# led_driver_iw339_v1.net
KiCad netlist of a schematic drawn in EAGLE
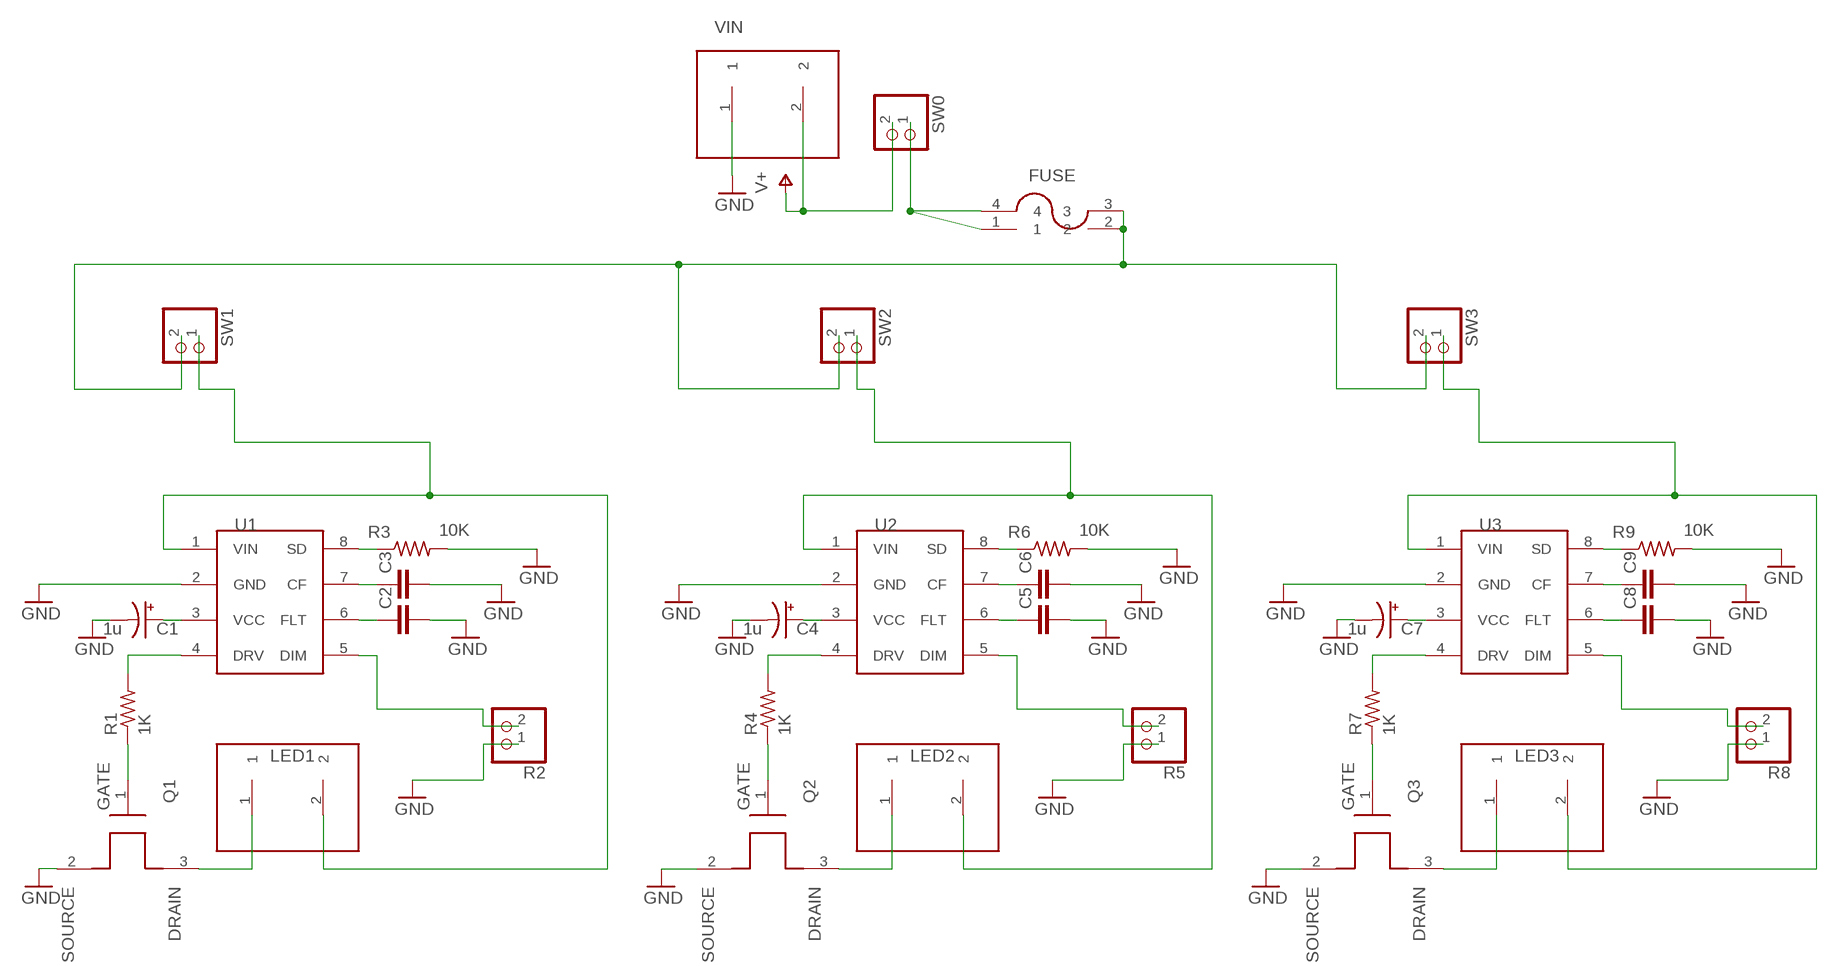
[diagram p0: schematic, sheet 1]

(export (version "E")
  (design (tool "Eeschema 10.0.6"))
  (components
    (comp (ref "C1")
      (value "1u")
      (footprint "eagle-import:E2-5")
      (libsource (lib "eagle-import") (part "CPOL-USE2-5"))
    )
    (comp (ref "C2")
      (value "0.1u")
      (footprint "eagle-import:C050-025X075")
      (libsource (lib "eagle-import") (part "THD_CAP"))
    )
    (comp (ref "C3")
      (value "1n")
      (footprint "eagle-import:C050-025X075")
      (libsource (lib "eagle-import") (part "THD_CAP"))
    )
    (comp (ref "C4")
      (value "1u")
      (footprint "eagle-import:E2-5")
      (libsource (lib "eagle-import") (part "CPOL-USE2-5"))
    )
    (comp (ref "C5")
      (value "0.1u")
      (footprint "eagle-import:C050-025X075")
      (libsource (lib "eagle-import") (part "THD_CAP"))
    )
    (comp (ref "C6")
      (value "1n")
      (footprint "eagle-import:C050-025X075")
      (libsource (lib "eagle-import") (part "THD_CAP"))
    )
    (comp (ref "C7")
      (value "1u")
      (footprint "eagle-import:E2-5")
      (libsource (lib "eagle-import") (part "CPOL-USE2-5"))
    )
    (comp (ref "C8")
      (value "0.1u")
      (footprint "eagle-import:C050-025X075")
      (libsource (lib "eagle-import") (part "THD_CAP"))
    )
    (comp (ref "C9")
      (value "1n")
      (footprint "eagle-import:C050-025X075")
      (libsource (lib "eagle-import") (part "THD_CAP"))
    )
    (comp (ref "FUSE")
      (value "5X20_FUSE_HOLDER")
      (footprint "eagle-import:5X20_FUSE_HOLDER")
      (libsource (lib "eagle-import") (part "5X20_FUSE_HOLDER"))
    )
    (comp (ref "LED1")
      (value "TERMINAL_BLOCK")
      (footprint "eagle-import:TERMINAL_BLOCK")
      (libsource (lib "eagle-import") (part "TERMINAL_BLOCK"))
    )
    (comp (ref "LED2")
      (value "TERMINAL_BLOCK")
      (footprint "eagle-import:TERMINAL_BLOCK")
      (libsource (lib "eagle-import") (part "TERMINAL_BLOCK"))
    )
    (comp (ref "LED3")
      (value "TERMINAL_BLOCK")
      (footprint "eagle-import:TERMINAL_BLOCK")
      (libsource (lib "eagle-import") (part "TERMINAL_BLOCK"))
    )
    (comp (ref "Q1")
      (value "DMTH6016LK3")
      (footprint "eagle-import:TO252")
      (libsource (lib "eagle-import") (part "DMTH6016LK3"))
    )
    (comp (ref "Q2")
      (value "DMTH6016LK3")
      (footprint "eagle-import:TO252")
      (libsource (lib "eagle-import") (part "DMTH6016LK3"))
    )
    (comp (ref "Q3")
      (value "DMTH6016LK3")
      (footprint "eagle-import:TO252")
      (libsource (lib "eagle-import") (part "DMTH6016LK3"))
    )
    (comp (ref "R1")
      (value "1K")
      (footprint "eagle-import:0207_10")
      (libsource (lib "eagle-import") (part "R-US_0207/10"))
    )
    (comp (ref "R2")
      (value "PINHD-1X2")
      (footprint "eagle-import:1X02")
      (libsource (lib "eagle-import") (part "PINHD-1X2"))
    )
    (comp (ref "R3")
      (value "10K")
      (footprint "eagle-import:0207_10")
      (libsource (lib "eagle-import") (part "R-US_0207/10"))
    )
    (comp (ref "R4")
      (value "1K")
      (footprint "eagle-import:0207_10")
      (libsource (lib "eagle-import") (part "R-US_0207/10"))
    )
    (comp (ref "R5")
      (value "PINHD-1X2")
      (footprint "eagle-import:1X02")
      (libsource (lib "eagle-import") (part "PINHD-1X2"))
    )
    (comp (ref "R6")
      (value "10K")
      (footprint "eagle-import:0207_10")
      (libsource (lib "eagle-import") (part "R-US_0207/10"))
    )
    (comp (ref "R7")
      (value "1K")
      (footprint "eagle-import:0207_10")
      (libsource (lib "eagle-import") (part "R-US_0207/10"))
    )
    (comp (ref "R8")
      (value "PINHD-1X2")
      (footprint "eagle-import:1X02")
      (libsource (lib "eagle-import") (part "PINHD-1X2"))
    )
    (comp (ref "R9")
      (value "10K")
      (footprint "eagle-import:0207_10")
      (libsource (lib "eagle-import") (part "R-US_0207/10"))
    )
    (comp (ref "SW0")
      (value "PINHD-1X2")
      (footprint "eagle-import:1X02")
      (libsource (lib "eagle-import") (part "PINHD-1X2"))
    )
    (comp (ref "SW1")
      (value "PINHD-1X2")
      (footprint "eagle-import:1X02")
      (libsource (lib "eagle-import") (part "PINHD-1X2"))
    )
    (comp (ref "SW2")
      (value "PINHD-1X2")
      (footprint "eagle-import:1X02")
      (libsource (lib "eagle-import") (part "PINHD-1X2"))
    )
    (comp (ref "SW3")
      (value "PINHD-1X2")
      (footprint "eagle-import:1X02")
      (libsource (lib "eagle-import") (part "PINHD-1X2"))
    )
    (comp (ref "U1")
      (value "IW339\"")
      (footprint "eagle-import:SOIC-8")
      (libsource (lib "eagle-import") (part "IW339{dblquote}"))
    )
    (comp (ref "U2")
      (value "IW339\"")
      (footprint "eagle-import:SOIC-8")
      (libsource (lib "eagle-import") (part "IW339{dblquote}"))
    )
    (comp (ref "U3")
      (value "IW339\"")
      (footprint "eagle-import:SOIC-8")
      (libsource (lib "eagle-import") (part "IW339{dblquote}"))
    )
    (comp (ref "VIN")
      (value "TERMINAL_BLOCK")
      (footprint "eagle-import:TERMINAL_BLOCK")
      (libsource (lib "eagle-import") (part "TERMINAL_BLOCK"))
    )
  )
  (nets
    (net (code "1") (name "GND") (class "Default")
      (node (ref "C1") (pin "-") (pinfunction "-_-") (pintype "passive"))
      (node (ref "C2") (pin "2") (pinfunction "2_2") (pintype "passive"))
      (node (ref "C3") (pin "2") (pinfunction "2_2") (pintype "passive"))
      (node (ref "C4") (pin "-") (pinfunction "-_-") (pintype "passive"))
      (node (ref "C5") (pin "2") (pinfunction "2_2") (pintype "passive"))
      (node (ref "C6") (pin "2") (pinfunction "2_2") (pintype "passive"))
      (node (ref "C7") (pin "-") (pinfunction "-_-") (pintype "passive"))
      (node (ref "C8") (pin "2") (pinfunction "2_2") (pintype "passive"))
      (node (ref "C9") (pin "2") (pinfunction "2_2") (pintype "passive"))
      (node (ref "Q1") (pin "2") (pinfunction "SOURCE_2") (pintype "bidirectional"))
      (node (ref "Q2") (pin "2") (pinfunction "SOURCE_2") (pintype "bidirectional"))
      (node (ref "Q3") (pin "2") (pinfunction "SOURCE_2") (pintype "bidirectional"))
      (node (ref "R2") (pin "1") (pinfunction "1_1") (pintype "passive"))
      (node (ref "R3") (pin "2") (pinfunction "2_2") (pintype "passive"))
      (node (ref "R5") (pin "1") (pinfunction "1_1") (pintype "passive"))
      (node (ref "R6") (pin "2") (pinfunction "2_2") (pintype "passive"))
      (node (ref "R8") (pin "1") (pinfunction "1_1") (pintype "passive"))
      (node (ref "R9") (pin "2") (pinfunction "2_2") (pintype "passive"))
      (node (ref "U1") (pin "2") (pinfunction "GND_2") (pintype "power_in"))
      (node (ref "U2") (pin "2") (pinfunction "GND_2") (pintype "power_in"))
      (node (ref "U3") (pin "2") (pinfunction "GND_2") (pintype "power_in"))
      (node (ref "VIN") (pin "1") (pinfunction "1_1") (pintype "bidirectional"))
    )
    (net (code "2") (name "Net-(FUSE-Pad1)") (class "Default")
      (node (ref "FUSE") (pin "1") (pinfunction "1_1") (pintype "bidirectional"))
      (node (ref "FUSE") (pin "4") (pinfunction "4_4") (pintype "bidirectional"))
      (node (ref "SW0") (pin "1") (pinfunction "1_1") (pintype "passive"))
    )
    (net (code "3") (name "Net-(FUSE-Pad2)") (class "Default")
      (node (ref "FUSE") (pin "2") (pinfunction "2_2") (pintype "bidirectional"))
      (node (ref "FUSE") (pin "3") (pinfunction "3_3") (pintype "bidirectional"))
      (node (ref "SW1") (pin "2") (pinfunction "2_2") (pintype "passive"))
      (node (ref "SW2") (pin "2") (pinfunction "2_2") (pintype "passive"))
      (node (ref "SW3") (pin "2") (pinfunction "2_2") (pintype "passive"))
    )
    (net (code "4") (name "Net-(Q1-DRAIN)") (class "Default")
      (node (ref "LED1") (pin "1") (pinfunction "1_1") (pintype "bidirectional"))
      (node (ref "Q1") (pin "3") (pinfunction "DRAIN_3") (pintype "bidirectional"))
    )
    (net (code "5") (name "Net-(Q1-GATE)") (class "Default")
      (node (ref "Q1") (pin "1") (pinfunction "GATE_1") (pintype "bidirectional"))
      (node (ref "R1") (pin "1") (pinfunction "1_1") (pintype "passive"))
    )
    (net (code "6") (name "Net-(Q2-DRAIN)") (class "Default")
      (node (ref "LED2") (pin "1") (pinfunction "1_1") (pintype "bidirectional"))
      (node (ref "Q2") (pin "3") (pinfunction "DRAIN_3") (pintype "bidirectional"))
    )
    (net (code "7") (name "Net-(Q2-GATE)") (class "Default")
      (node (ref "Q2") (pin "1") (pinfunction "GATE_1") (pintype "bidirectional"))
      (node (ref "R4") (pin "1") (pinfunction "1_1") (pintype "passive"))
    )
    (net (code "8") (name "Net-(Q3-DRAIN)") (class "Default")
      (node (ref "LED3") (pin "1") (pinfunction "1_1") (pintype "bidirectional"))
      (node (ref "Q3") (pin "3") (pinfunction "DRAIN_3") (pintype "bidirectional"))
    )
    (net (code "9") (name "Net-(Q3-GATE)") (class "Default")
      (node (ref "Q3") (pin "1") (pinfunction "GATE_1") (pintype "bidirectional"))
      (node (ref "R7") (pin "1") (pinfunction "1_1") (pintype "passive"))
    )
    (net (code "10") (name "Net-(U1-CF)") (class "Default")
      (node (ref "C3") (pin "1") (pinfunction "1_1") (pintype "passive"))
      (node (ref "U1") (pin "7") (pinfunction "CF_7") (pintype "input"))
    )
    (net (code "11") (name "Net-(U1-DIM)") (class "Default")
      (node (ref "R2") (pin "2") (pinfunction "2_2") (pintype "passive"))
      (node (ref "U1") (pin "5") (pinfunction "DIM_5") (pintype "input"))
    )
    (net (code "12") (name "Net-(U1-DRV)") (class "Default")
      (node (ref "R1") (pin "2") (pinfunction "2_2") (pintype "passive"))
      (node (ref "U1") (pin "4") (pinfunction "DRV_4") (pintype "output"))
    )
    (net (code "13") (name "Net-(U1-FLT)") (class "Default")
      (node (ref "C2") (pin "1") (pinfunction "1_1") (pintype "passive"))
      (node (ref "U1") (pin "6") (pinfunction "FLT_6") (pintype "input"))
    )
    (net (code "14") (name "Net-(U1-SD)") (class "Default")
      (node (ref "R3") (pin "1") (pinfunction "1_1") (pintype "passive"))
      (node (ref "U1") (pin "8") (pinfunction "SD_8") (pintype "input"))
    )
    (net (code "15") (name "Net-(U1-VCC)") (class "Default")
      (node (ref "C1") (pin "+") (pinfunction "+_+") (pintype "passive"))
      (node (ref "U1") (pin "3") (pinfunction "VCC_3") (pintype "power_in"))
    )
    (net (code "16") (name "Net-(U1-VIN)") (class "Default")
      (node (ref "LED1") (pin "2") (pinfunction "2_2") (pintype "bidirectional"))
      (node (ref "SW1") (pin "1") (pinfunction "1_1") (pintype "passive"))
      (node (ref "U1") (pin "1") (pinfunction "VIN_1") (pintype "power_in"))
    )
    (net (code "17") (name "Net-(U2-CF)") (class "Default")
      (node (ref "C6") (pin "1") (pinfunction "1_1") (pintype "passive"))
      (node (ref "U2") (pin "7") (pinfunction "CF_7") (pintype "input"))
    )
    (net (code "18") (name "Net-(U2-DIM)") (class "Default")
      (node (ref "R5") (pin "2") (pinfunction "2_2") (pintype "passive"))
      (node (ref "U2") (pin "5") (pinfunction "DIM_5") (pintype "input"))
    )
    (net (code "19") (name "Net-(U2-DRV)") (class "Default")
      (node (ref "R4") (pin "2") (pinfunction "2_2") (pintype "passive"))
      (node (ref "U2") (pin "4") (pinfunction "DRV_4") (pintype "output"))
    )
    (net (code "20") (name "Net-(U2-FLT)") (class "Default")
      (node (ref "C5") (pin "1") (pinfunction "1_1") (pintype "passive"))
      (node (ref "U2") (pin "6") (pinfunction "FLT_6") (pintype "input"))
    )
    (net (code "21") (name "Net-(U2-SD)") (class "Default")
      (node (ref "R6") (pin "1") (pinfunction "1_1") (pintype "passive"))
      (node (ref "U2") (pin "8") (pinfunction "SD_8") (pintype "input"))
    )
    (net (code "22") (name "Net-(U2-VCC)") (class "Default")
      (node (ref "C4") (pin "+") (pinfunction "+_+") (pintype "passive"))
      (node (ref "U2") (pin "3") (pinfunction "VCC_3") (pintype "power_in"))
    )
    (net (code "23") (name "Net-(U2-VIN)") (class "Default")
      (node (ref "LED2") (pin "2") (pinfunction "2_2") (pintype "bidirectional"))
      (node (ref "SW2") (pin "1") (pinfunction "1_1") (pintype "passive"))
      (node (ref "U2") (pin "1") (pinfunction "VIN_1") (pintype "power_in"))
    )
    (net (code "24") (name "Net-(U3-CF)") (class "Default")
      (node (ref "C9") (pin "1") (pinfunction "1_1") (pintype "passive"))
      (node (ref "U3") (pin "7") (pinfunction "CF_7") (pintype "input"))
    )
    (net (code "25") (name "Net-(U3-DIM)") (class "Default")
      (node (ref "R8") (pin "2") (pinfunction "2_2") (pintype "passive"))
      (node (ref "U3") (pin "5") (pinfunction "DIM_5") (pintype "input"))
    )
    (net (code "26") (name "Net-(U3-DRV)") (class "Default")
      (node (ref "R7") (pin "2") (pinfunction "2_2") (pintype "passive"))
      (node (ref "U3") (pin "4") (pinfunction "DRV_4") (pintype "output"))
    )
    (net (code "27") (name "Net-(U3-FLT)") (class "Default")
      (node (ref "C8") (pin "1") (pinfunction "1_1") (pintype "passive"))
      (node (ref "U3") (pin "6") (pinfunction "FLT_6") (pintype "input"))
    )
    (net (code "28") (name "Net-(U3-SD)") (class "Default")
      (node (ref "R9") (pin "1") (pinfunction "1_1") (pintype "passive"))
      (node (ref "U3") (pin "8") (pinfunction "SD_8") (pintype "input"))
    )
    (net (code "29") (name "Net-(U3-VCC)") (class "Default")
      (node (ref "C7") (pin "+") (pinfunction "+_+") (pintype "passive"))
      (node (ref "U3") (pin "3") (pinfunction "VCC_3") (pintype "power_in"))
    )
    (net (code "30") (name "Net-(U3-VIN)") (class "Default")
      (node (ref "LED3") (pin "2") (pinfunction "2_2") (pintype "bidirectional"))
      (node (ref "SW3") (pin "1") (pinfunction "1_1") (pintype "passive"))
      (node (ref "U3") (pin "1") (pinfunction "VIN_1") (pintype "power_in"))
    )
    (net (code "31") (name "V+") (class "Default")
      (node (ref "SW0") (pin "2") (pinfunction "2_2") (pintype "passive"))
      (node (ref "VIN") (pin "2") (pinfunction "2_2") (pintype "bidirectional"))
    )
  )
)
